# OpenLCD-Dimension_For_Spec.net
KiCad netlist of a schematic drawn in EAGLE
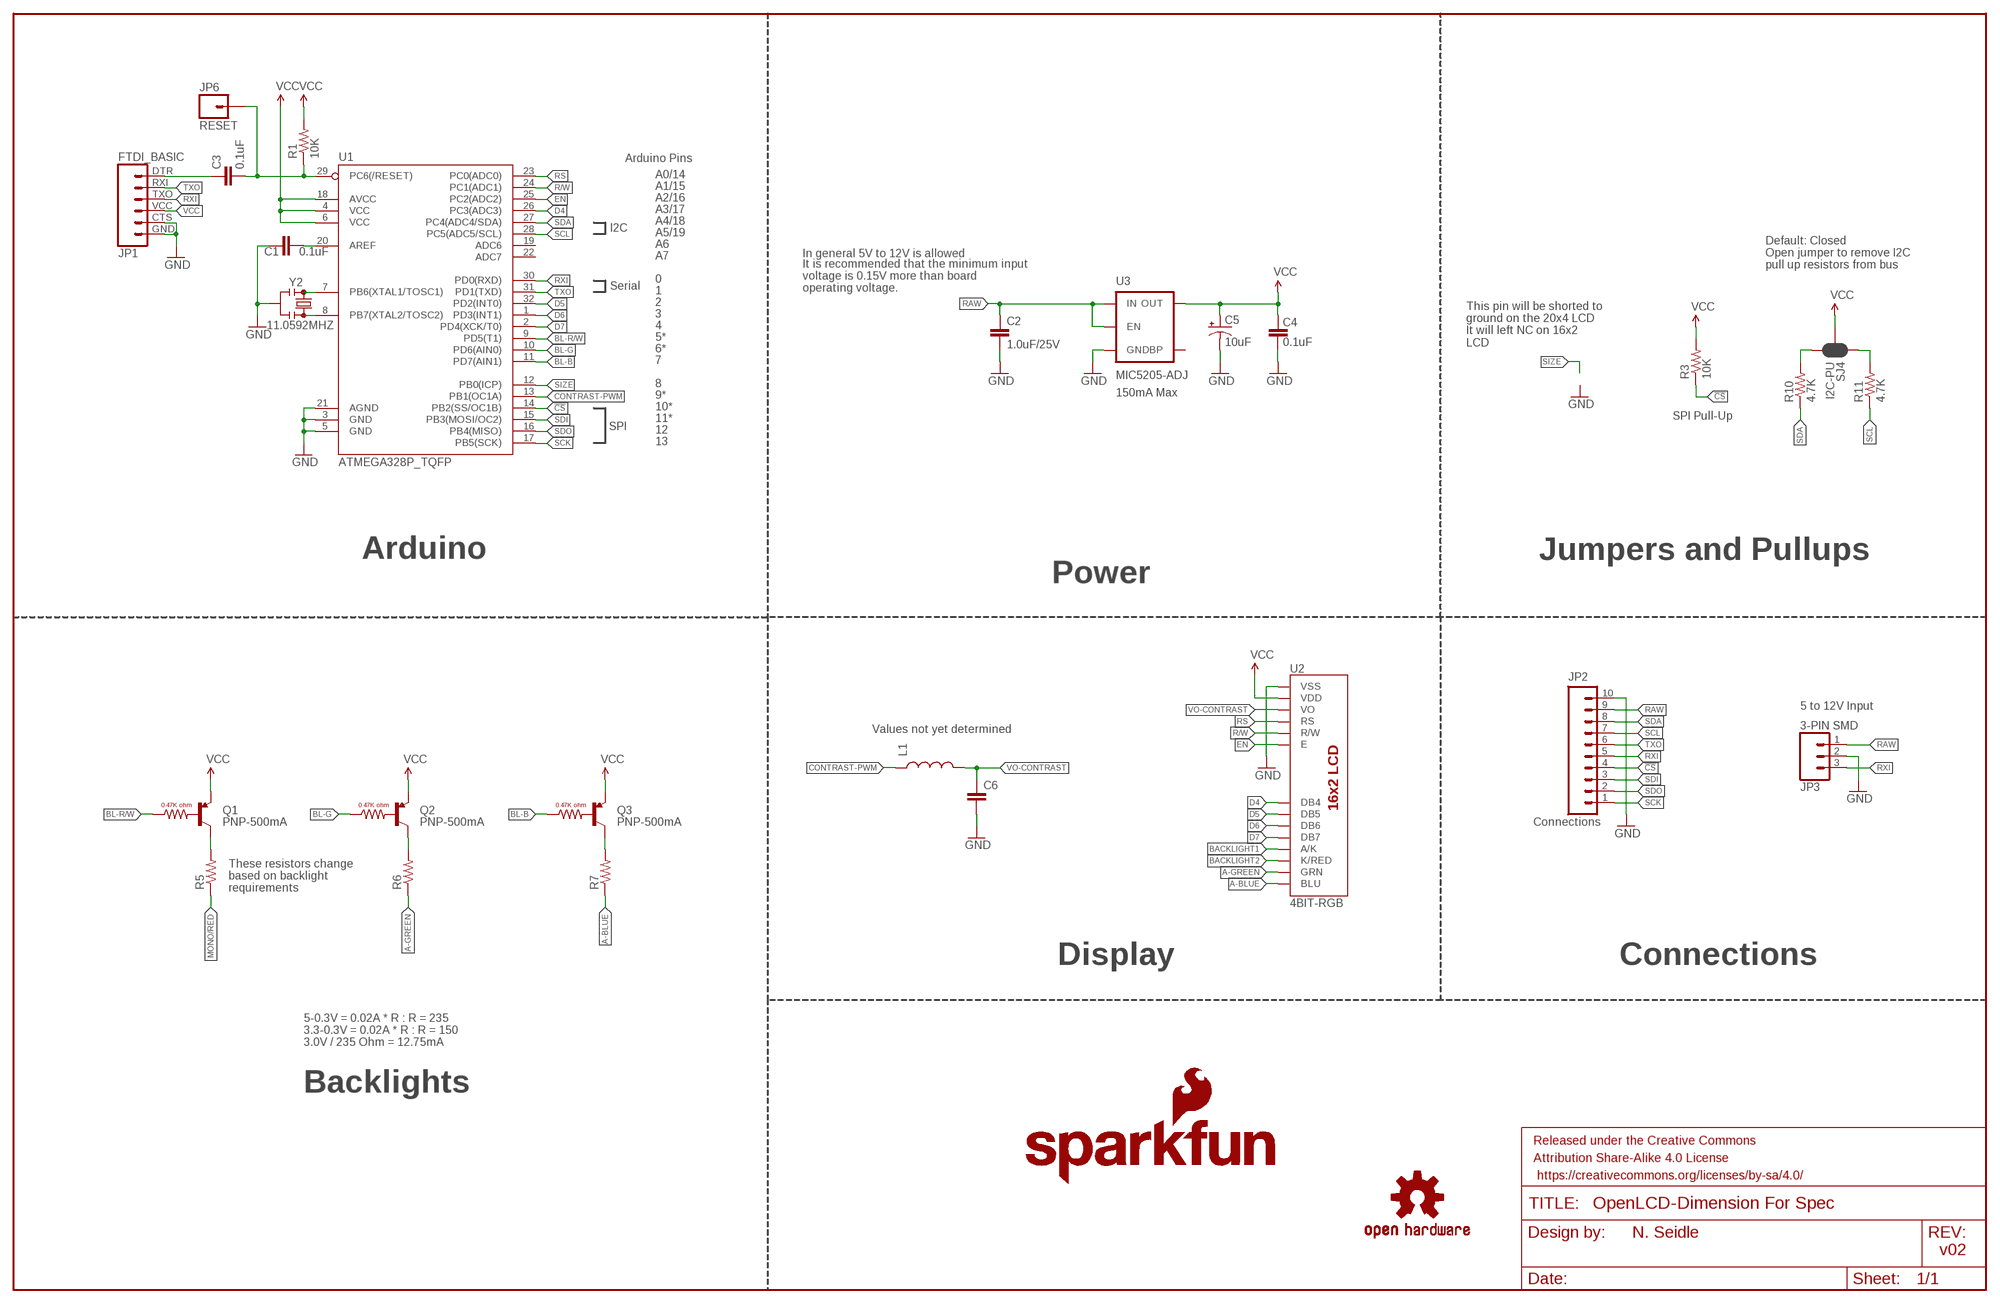
[diagram p0: schematic, sheet 1]

(export (version "E")
  (design (tool "Eeschema 10.0.6"))
  (components
    (comp (ref "C1")
      (value "0.1uF")
      (footprint "eagle-import:0603-CAP")
      (libsource (lib "eagle-import") (part "0.1UF-25V(+80/-20%)(0603)"))
    )
    (comp (ref "C2")
      (value "1.0uF/25V")
      (footprint "eagle-import:0805-CAP")
      (libsource (lib "eagle-import") (part "1.0UF-25V-+80/-20(0805){dblquote}"))
    )
    (comp (ref "C3")
      (value "0.1uF")
      (footprint "eagle-import:0603-CAP")
      (libsource (lib "eagle-import") (part "0.1UF-25V(+80/-20%)(0603)"))
    )
    (comp (ref "C4")
      (value "0.1uF")
      (footprint "eagle-import:0603-CAP")
      (libsource (lib "eagle-import") (part "0.1UF-25V(+80/-20%)(0603)"))
    )
    (comp (ref "C5")
      (value "10uF")
      (footprint "eagle-import:EIA3216")
      (libsource (lib "eagle-import") (part "10UF-16V-10%(TANT)"))
    )
    (comp (ref "C6")
      (value "CAP0603-CAP")
      (footprint "eagle-import:0603-CAP")
      (libsource (lib "eagle-import") (part "CAP0603-CAP"))
    )
    (comp (ref "FRAME1")
      (value "FRAME-LEDGER")
      (footprint "eagle-import:CREATIVE_COMMONS")
      (libsource (lib "eagle-import") (part "FRAME-LEDGER"))
    )
    (comp (ref "JP1")
      (value "FTDI_BASIC")
      (footprint "eagle-import:FTDI_BASIC")
      (libsource (lib "eagle-import") (part "FTDI_BASICPTH"))
    )
    (comp (ref "JP2")
      (value "Connections")
      (footprint "eagle-import:1X10")
      (libsource (lib "eagle-import") (part "M10SILK_FEMALE_PTH"))
    )
    (comp (ref "JP3")
      (value "3-PIN SMD")
      (footprint "eagle-import:JST-3-PTH-VERT")
      (libsource (lib "eagle-import") (part "M03JST-PTH-VERT"))
    )
    (comp (ref "JP6")
      (value "RESET")
      (footprint "eagle-import:1X01")
      (libsource (lib "eagle-import") (part "M01PTH"))
    )
    (comp (ref "L1")
      (value "INDUCTOR0603")
      (footprint "eagle-import:0603")
      (libsource (lib "eagle-import") (part "INDUCTOR0603"))
    )
    (comp (ref "LOGO1")
      (value "SFE_LOGO_NAME_FLAME.1_INCH")
      (footprint "eagle-import:SFE_LOGO_NAME_FLAME_.1")
      (libsource (lib "eagle-import") (part "SFE_LOGO_NAME_FLAME.1_INCH"))
    )
    (comp (ref "Q1")
      (value "PNP-500mA")
      (footprint "eagle-import:SOT23-3")
      (libsource (lib "eagle-import") (part "TRANSISTOR-PNP-DDTB142TC"))
    )
    (comp (ref "Q2")
      (value "PNP-500mA")
      (footprint "eagle-import:SOT23-3")
      (libsource (lib "eagle-import") (part "TRANSISTOR-PNP-DDTB142TC"))
    )
    (comp (ref "Q3")
      (value "PNP-500mA")
      (footprint "eagle-import:SOT23-3")
      (libsource (lib "eagle-import") (part "TRANSISTOR-PNP-DDTB142TC"))
    )
    (comp (ref "R1")
      (value "10K")
      (footprint "eagle-import:0603-RES")
      (libsource (lib "eagle-import") (part "10KOHM-1/10W-1%(0603)0603"))
    )
    (comp (ref "R3")
      (value "10K")
      (footprint "eagle-import:0603-RES")
      (libsource (lib "eagle-import") (part "10KOHM-1/10W-1%(0603)0603"))
    )
    (comp (ref "R5")
      (value "240")
      (footprint "eagle-import:0603-RES")
      (libsource (lib "eagle-import") (part "240OHM1/10W1%(0603)"))
    )
    (comp (ref "R6")
      (value "240")
      (footprint "eagle-import:0603-RES")
      (libsource (lib "eagle-import") (part "240OHM1/10W1%(0603)"))
    )
    (comp (ref "R7")
      (value "240")
      (footprint "eagle-import:0603-RES")
      (libsource (lib "eagle-import") (part "240OHM1/10W1%(0603)"))
    )
    (comp (ref "R10")
      (value "4.7K")
      (footprint "eagle-import:0603-RES")
      (libsource (lib "eagle-import") (part "4.7KOHM-1/10W-1%(0603)"))
    )
    (comp (ref "R11")
      (value "4.7K")
      (footprint "eagle-import:0603-RES")
      (libsource (lib "eagle-import") (part "4.7KOHM-1/10W-1%(0603)"))
    )
    (comp (ref "SJ4")
      (value "I2C-PU")
      (footprint "eagle-import:PAD-JUMPER-3-NC_BY_PASTE_YES_SILK_FULL_BOX")
      (libsource (lib "eagle-import") (part "JUMPER-PAD-3-NC_BY_PASTE"))
    )
    (comp (ref "U$4")
      (value "OSHW-LOGOS")
      (footprint "eagle-import:OSHW-LOGO-S")
      (libsource (lib "eagle-import") (part "OSHW-LOGOS"))
    )
    (comp (ref "U1")
      (value "ATMEGA328P_TQFP")
      (footprint "eagle-import:TQFP32-08")
      (libsource (lib "eagle-import") (part "ATMEGA328P_TQFP"))
    )
    (comp (ref "U2")
      (value "4BIT-RGB")
      (footprint "eagle-import:LCD-16X2_NOSILK-KIT-4BIT")
      (libsource (lib "eagle-import") (part "LCD-16X2-MINMIN4-RGB"))
    )
    (comp (ref "U3")
      (value "MIC5205-ADJ")
      (footprint "eagle-import:SOT23-5")
      (libsource (lib "eagle-import") (part "V_REG_MIC5205ADJ"))
    )
    (comp (ref "Y2")
      (value "11.0592MHZ")
      (footprint "eagle-import:RESONATOR-SMD")
      (libsource (lib "eagle-import") (part "RESONATOR8MHZ"))
    )
  )
  (nets
    (net (code "1") (name "/~{CS}") (class "Default")
      (node (ref "JP2") (pin "4") (pinfunction "4_4") (pintype "passive"))
      (node (ref "R3") (pin "1") (pinfunction "1_1") (pintype "passive"))
      (node (ref "U1") (pin "14") (pinfunction "PB2(SS/OC1B)_14") (pintype "bidirectional"))
    )
    (net (code "2") (name "A-BLUE") (class "Default")
      (node (ref "R7") (pin "1") (pinfunction "1_1") (pintype "passive"))
      (node (ref "U2") (pin "18") (pinfunction "BLU_18") (pintype "power_in"))
    )
    (net (code "3") (name "A-GREEN") (class "Default")
      (node (ref "R6") (pin "1") (pinfunction "1_1") (pintype "passive"))
      (node (ref "U2") (pin "17") (pinfunction "GRN_17") (pintype "power_in"))
    )
    (net (code "4") (name "BACKLIGHT1") (class "Default")
      (node (ref "U2") (pin "15") (pinfunction "A/K_15") (pintype "power_in"))
    )
    (net (code "5") (name "BACKLIGHT2") (class "Default")
      (node (ref "U2") (pin "16") (pinfunction "K/RED_16") (pintype "power_in"))
    )
    (net (code "6") (name "BL-B") (class "Default")
      (node (ref "Q3") (pin "1") (pinfunction "B_1") (pintype "passive"))
      (node (ref "U1") (pin "11") (pinfunction "PD7(AIN1)_11") (pintype "bidirectional"))
    )
    (net (code "7") (name "BL-G") (class "Default")
      (node (ref "Q2") (pin "1") (pinfunction "B_1") (pintype "passive"))
      (node (ref "U1") (pin "10") (pinfunction "PD6(AIN0)_10") (pintype "bidirectional"))
    )
    (net (code "8") (name "BL-R{slash}W") (class "Default")
      (node (ref "Q1") (pin "1") (pinfunction "B_1") (pintype "passive"))
      (node (ref "U1") (pin "9") (pinfunction "PD5(T1)_9") (pintype "bidirectional"))
    )
    (net (code "9") (name "CONTRAST-PWM") (class "Default")
      (node (ref "L1") (pin "1") (pinfunction "1_1") (pintype "passive"))
      (node (ref "U1") (pin "13") (pinfunction "PB1(OC1A)_13") (pintype "bidirectional"))
    )
    (net (code "10") (name "D4") (class "Default")
      (node (ref "U1") (pin "26") (pinfunction "PC3(ADC3)_26") (pintype "bidirectional"))
      (node (ref "U2") (pin "11") (pinfunction "DB4_11") (pintype "bidirectional"))
    )
    (net (code "11") (name "D5") (class "Default")
      (node (ref "U1") (pin "32") (pinfunction "PD2(INT0)_32") (pintype "bidirectional"))
      (node (ref "U2") (pin "12") (pinfunction "DB5_12") (pintype "bidirectional"))
    )
    (net (code "12") (name "D6") (class "Default")
      (node (ref "U1") (pin "1") (pinfunction "PD3(INT1)_1") (pintype "bidirectional"))
      (node (ref "U2") (pin "13") (pinfunction "DB6_13") (pintype "bidirectional"))
    )
    (net (code "13") (name "D7") (class "Default")
      (node (ref "U1") (pin "2") (pinfunction "PD4(XCK/T0)_2") (pintype "bidirectional"))
      (node (ref "U2") (pin "14") (pinfunction "DB7_14") (pintype "bidirectional"))
    )
    (net (code "14") (name "EN") (class "Default")
      (node (ref "U1") (pin "25") (pinfunction "PC2(ADC2)_25") (pintype "bidirectional"))
      (node (ref "U2") (pin "6") (pinfunction "E_6") (pintype "input"))
    )
    (net (code "15") (name "GND") (class "Default")
      (node (ref "C1") (pin "1") (pinfunction "1_1") (pintype "passive"))
      (node (ref "C2") (pin "2") (pinfunction "2_2") (pintype "passive"))
      (node (ref "C4") (pin "1") (pinfunction "1_1") (pintype "passive"))
      (node (ref "C5") (pin "C") (pinfunction "-_C") (pintype "passive"))
      (node (ref "C6") (pin "2") (pinfunction "2_2") (pintype "passive"))
      (node (ref "JP1") (pin "CTS") (pinfunction "5_CTS") (pintype "passive"))
      (node (ref "JP1") (pin "GND") (pinfunction "6_GND") (pintype "passive"))
      (node (ref "JP2") (pin "10") (pinfunction "10_10") (pintype "passive"))
      (node (ref "JP3") (pin "2") (pinfunction "2_2") (pintype "passive"))
      (node (ref "U1") (pin "21") (pinfunction "AGND_21") (pintype "bidirectional"))
      (node (ref "U1") (pin "3") (pinfunction "GND_3") (pintype "bidirectional"))
      (node (ref "U1") (pin "5") (pinfunction "GND_5") (pintype "bidirectional"))
      (node (ref "U2") (pin "1") (pinfunction "VSS_1") (pintype "power_in"))
      (node (ref "U3") (pin "2") (pinfunction "GND_2") (pintype "input"))
      (node (ref "Y2") (pin "2") (pinfunction "2_2") (pintype "passive"))
    )
    (net (code "16") (name "MONO{slash}RED") (class "Default")
      (node (ref "R5") (pin "1") (pinfunction "1_1") (pintype "passive"))
    )
    (net (code "17") (name "Net-(JP1-1)") (class "Default")
      (node (ref "C3") (pin "1") (pinfunction "1_1") (pintype "passive"))
      (node (ref "JP1") (pin "DTR") (pinfunction "1_DTR") (pintype "passive"))
    )
    (net (code "18") (name "Net-(Q1-C)") (class "Default")
      (node (ref "Q1") (pin "3") (pinfunction "C_3") (pintype "passive"))
      (node (ref "R5") (pin "2") (pinfunction "2_2") (pintype "passive"))
    )
    (net (code "19") (name "Net-(Q2-C)") (class "Default")
      (node (ref "Q2") (pin "3") (pinfunction "C_3") (pintype "passive"))
      (node (ref "R6") (pin "2") (pinfunction "2_2") (pintype "passive"))
    )
    (net (code "20") (name "Net-(Q3-C)") (class "Default")
      (node (ref "Q3") (pin "3") (pinfunction "C_3") (pintype "passive"))
      (node (ref "R7") (pin "2") (pinfunction "2_2") (pintype "passive"))
    )
    (net (code "21") (name "Net-(R10-Pad2)") (class "Default")
      (node (ref "R10") (pin "2") (pinfunction "2_2") (pintype "passive"))
      (node (ref "SJ4") (pin "3") (pinfunction "3_3") (pintype "passive"))
    )
    (net (code "22") (name "Net-(R11-Pad2)") (class "Default")
      (node (ref "R11") (pin "2") (pinfunction "2_2") (pintype "passive"))
      (node (ref "SJ4") (pin "1") (pinfunction "1_1") (pintype "passive"))
    )
    (net (code "23") (name "Net-(U1-AREF)") (class "Default")
      (node (ref "C1") (pin "2") (pinfunction "2_2") (pintype "passive"))
      (node (ref "U1") (pin "20") (pinfunction "AREF_20") (pintype "bidirectional"))
    )
    (net (code "24") (name "Net-(U1-PB6(XTAL1{slash}TOSC1))") (class "Default")
      (node (ref "U1") (pin "7") (pinfunction "PB6(XTAL1/TOSC1)_7") (pintype "bidirectional"))
      (node (ref "Y2") (pin "1") (pinfunction "1_1") (pintype "passive"))
    )
    (net (code "25") (name "Net-(U1-PB7(XTAL2{slash}TOSC2))") (class "Default")
      (node (ref "U1") (pin "8") (pinfunction "PB7(XTAL2/TOSC2)_8") (pintype "bidirectional"))
      (node (ref "Y2") (pin "3") (pinfunction "3_3") (pintype "passive"))
    )
    (net (code "26") (name "Net-(U1-PC6({slash}RESET))") (class "Default")
      (node (ref "C3") (pin "2") (pinfunction "2_2") (pintype "passive"))
      (node (ref "JP6") (pin "1") (pinfunction "1_1") (pintype "passive"))
      (node (ref "R1") (pin "1") (pinfunction "1_1") (pintype "passive"))
      (node (ref "U1") (pin "29") (pinfunction "PC6(/RESET)_29") (pintype "bidirectional"))
    )
    (net (code "27") (name "RAW") (class "Default")
      (node (ref "C2") (pin "1") (pinfunction "1_1") (pintype "passive"))
      (node (ref "JP2") (pin "9") (pinfunction "9_9") (pintype "passive"))
      (node (ref "JP3") (pin "1") (pinfunction "1_1") (pintype "passive"))
      (node (ref "U3") (pin "1") (pinfunction "IN_1") (pintype "input"))
      (node (ref "U3") (pin "3") (pinfunction "EN_3") (pintype "input"))
    )
    (net (code "28") (name "RS") (class "Default")
      (node (ref "U1") (pin "23") (pinfunction "PC0(ADC0)_23") (pintype "bidirectional"))
      (node (ref "U2") (pin "4") (pinfunction "RS_4") (pintype "input"))
    )
    (net (code "29") (name "RXI") (class "Default")
      (node (ref "JP1") (pin "TXO") (pinfunction "3_TXO") (pintype "passive"))
      (node (ref "JP2") (pin "5") (pinfunction "5_5") (pintype "passive"))
      (node (ref "JP3") (pin "3") (pinfunction "3_3") (pintype "passive"))
      (node (ref "U1") (pin "30") (pinfunction "PD0(RXD)_30") (pintype "bidirectional"))
    )
    (net (code "30") (name "R{slash}W") (class "Default")
      (node (ref "U1") (pin "24") (pinfunction "PC1(ADC1)_24") (pintype "bidirectional"))
      (node (ref "U2") (pin "5") (pinfunction "R/W_5") (pintype "input"))
    )
    (net (code "31") (name "SCK") (class "Default")
      (node (ref "JP2") (pin "1") (pinfunction "1_1") (pintype "passive"))
      (node (ref "U1") (pin "17") (pinfunction "PB5(SCK)_17") (pintype "bidirectional"))
    )
    (net (code "32") (name "SCL") (class "Default")
      (node (ref "JP2") (pin "7") (pinfunction "7_7") (pintype "passive"))
      (node (ref "R11") (pin "1") (pinfunction "1_1") (pintype "passive"))
      (node (ref "U1") (pin "28") (pinfunction "PC5(ADC5/SCL)_28") (pintype "bidirectional"))
    )
    (net (code "33") (name "SDA") (class "Default")
      (node (ref "JP2") (pin "8") (pinfunction "8_8") (pintype "passive"))
      (node (ref "R10") (pin "1") (pinfunction "1_1") (pintype "passive"))
      (node (ref "U1") (pin "27") (pinfunction "PC4(ADC4/SDA)_27") (pintype "bidirectional"))
    )
    (net (code "34") (name "SDI") (class "Default")
      (node (ref "JP2") (pin "3") (pinfunction "3_3") (pintype "passive"))
      (node (ref "U1") (pin "15") (pinfunction "PB3(MOSI/OC2)_15") (pintype "bidirectional"))
    )
    (net (code "35") (name "SDO") (class "Default")
      (node (ref "JP2") (pin "2") (pinfunction "2_2") (pintype "passive"))
      (node (ref "U1") (pin "16") (pinfunction "PB4(MISO)_16") (pintype "bidirectional"))
    )
    (net (code "36") (name "SIZE") (class "Default")
      (node (ref "U1") (pin "12") (pinfunction "PB0(ICP)_12") (pintype "bidirectional"))
    )
    (net (code "37") (name "TXO") (class "Default")
      (node (ref "JP1") (pin "RXI") (pinfunction "2_RXI") (pintype "passive"))
      (node (ref "JP2") (pin "6") (pinfunction "6_6") (pintype "passive"))
      (node (ref "U1") (pin "31") (pinfunction "PD1(TXD)_31") (pintype "bidirectional"))
    )
    (net (code "38") (name "VCC") (class "Default")
      (node (ref "C4") (pin "2") (pinfunction "2_2") (pintype "passive"))
      (node (ref "C5") (pin "A") (pinfunction "+_A") (pintype "passive"))
      (node (ref "JP1") (pin "VCC") (pinfunction "4_VCC") (pintype "passive"))
      (node (ref "Q1") (pin "2") (pinfunction "E_2") (pintype "passive"))
      (node (ref "Q2") (pin "2") (pinfunction "E_2") (pintype "passive"))
      (node (ref "Q3") (pin "2") (pinfunction "E_2") (pintype "passive"))
      (node (ref "R1") (pin "2") (pinfunction "2_2") (pintype "passive"))
      (node (ref "R3") (pin "2") (pinfunction "2_2") (pintype "passive"))
      (node (ref "SJ4") (pin "2") (pinfunction "2_2") (pintype "passive"))
      (node (ref "U1") (pin "18") (pinfunction "AVCC_18") (pintype "bidirectional"))
      (node (ref "U1") (pin "4") (pinfunction "VCC_4") (pintype "bidirectional"))
      (node (ref "U1") (pin "6") (pinfunction "VCC_6") (pintype "bidirectional"))
      (node (ref "U2") (pin "2") (pinfunction "VDD_2") (pintype "power_in"))
      (node (ref "U3") (pin "5") (pinfunction "OUT_5") (pintype "passive"))
    )
    (net (code "39") (name "VO-CONTRAST") (class "Default")
      (node (ref "C6") (pin "1") (pinfunction "1_1") (pintype "passive"))
      (node (ref "L1") (pin "2") (pinfunction "2_2") (pintype "passive"))
      (node (ref "U2") (pin "3") (pinfunction "VO_3") (pintype "bidirectional"))
    )
    (net (code "40") (name "unconnected-(U1-ADC6-Pad19)") (class "Default")
      (node (ref "U1") (pin "19") (pinfunction "ADC6_19") (pintype "bidirectional"))
    )
    (net (code "41") (name "unconnected-(U1-ADC7-Pad22)") (class "Default")
      (node (ref "U1") (pin "22") (pinfunction "ADC7_22") (pintype "bidirectional"))
    )
    (net (code "42") (name "unconnected-(U3-BP-Pad4)") (class "Default")
      (node (ref "U3") (pin "4") (pinfunction "BP_4") (pintype "input"))
    )
  )
)
